# breakout_v0_4.net
KiCad netlist of a schematic drawn in EAGLE
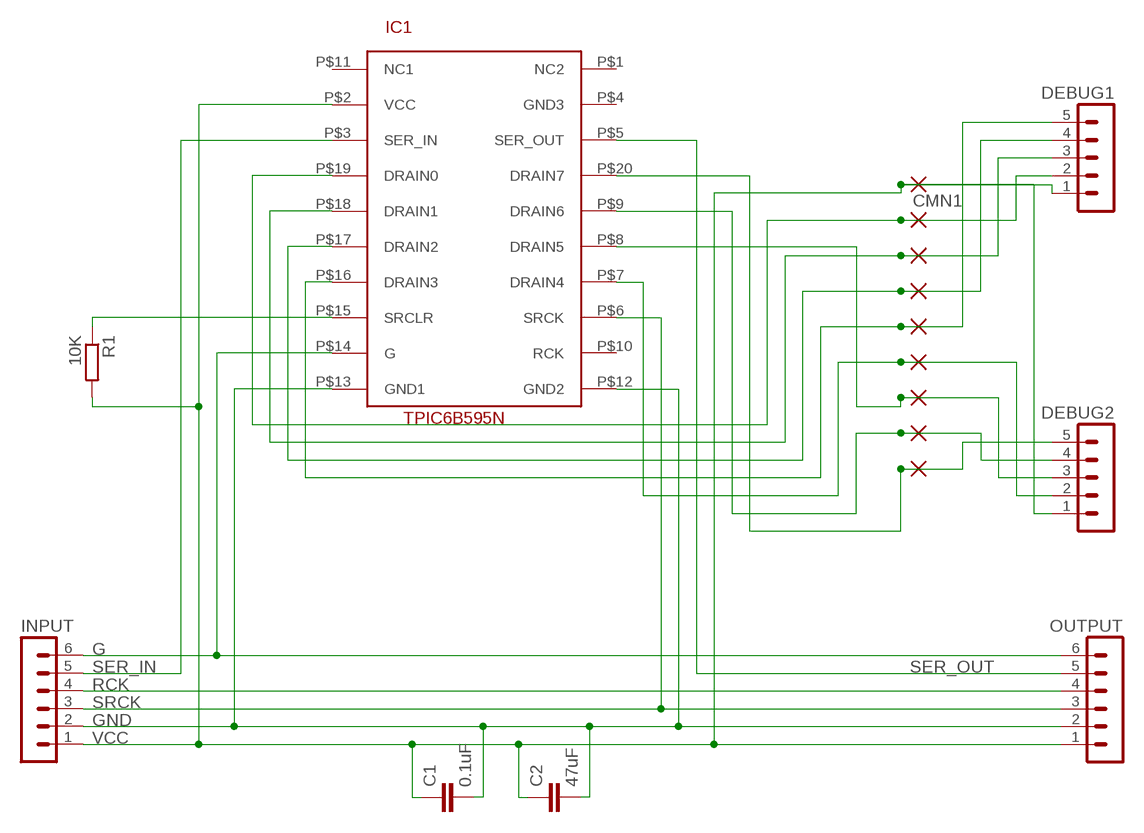
[diagram p0: schematic, sheet 1]

(export (version "E")
  (design (tool "Eeschema 10.0.6"))
  (components
    (comp (ref "C1")
      (value "0.1uF")
      (footprint "eagle-import:RCL_C025-025X050")
      (libsource (lib "eagle-import") (part "RCL_C-EU025-025X050"))
    )
    (comp (ref "C2")
      (value "47uF")
      (footprint "eagle-import:RCL_C025-025X050")
      (libsource (lib "eagle-import") (part "RCL_C-EU025-025X050"))
    )
    (comp (ref "CMN1")
      (value "1,6/0,8")
      (footprint "eagle-import:1,6_0,8")
      (libsource (lib "eagle-import") (part "1,6/0,8"))
    )
    (comp (ref "DEBUG1")
      (value "MA05-1")
      (footprint "eagle-import:MA05-1")
      (libsource (lib "eagle-import") (part "MA05-1"))
    )
    (comp (ref "DEBUG2")
      (value "MA05-1")
      (footprint "eagle-import:MA05-1")
      (libsource (lib "eagle-import") (part "MA05-1"))
    )
    (comp (ref "DEC1")
      (value "1,6/0,8")
      (footprint "eagle-import:1,6_0,8")
      (libsource (lib "eagle-import") (part "1,6/0,8"))
    )
    (comp (ref "INPUT")
      (value "CON-LSTB_MA06-1")
      (footprint "eagle-import:CON-LSTB_MA06-1")
      (libsource (lib "eagle-import") (part "CON-LSTB_MA06-1"))
    )
    (comp (ref "OUTPUT")
      (value "CON-LSTB_MA06-1")
      (footprint "eagle-import:CON-LSTB_MA06-1")
      (libsource (lib "eagle-import") (part "CON-LSTB_MA06-1"))
    )
    (comp (ref "R1")
      (value "10K")
      (footprint "eagle-import:RCL_0207_7")
      (libsource (lib "eagle-import") (part "RCL_R-EU_0207/7"))
    )
    (comp (ref "SEGA1")
      (value "1,6/0,8")
      (footprint "eagle-import:1,6_0,8")
      (libsource (lib "eagle-import") (part "1,6/0,8"))
    )
    (comp (ref "SEGB1")
      (value "1,6/0,8")
      (footprint "eagle-import:1,6_0,8")
      (libsource (lib "eagle-import") (part "1,6/0,8"))
    )
    (comp (ref "SEGC1")
      (value "1,6/0,8")
      (footprint "eagle-import:1,6_0,8")
      (libsource (lib "eagle-import") (part "1,6/0,8"))
    )
    (comp (ref "SEGD1")
      (value "1,6/0,8")
      (footprint "eagle-import:1,6_0,8")
      (libsource (lib "eagle-import") (part "1,6/0,8"))
    )
    (comp (ref "SEGE1")
      (value "1,6/0,8")
      (footprint "eagle-import:1,6_0,8")
      (libsource (lib "eagle-import") (part "1,6/0,8"))
    )
    (comp (ref "SEGF1")
      (value "1,6/0,8")
      (footprint "eagle-import:1,6_0,8")
      (libsource (lib "eagle-import") (part "1,6/0,8"))
    )
    (comp (ref "SEGG1")
      (value "1,6/0,8")
      (footprint "eagle-import:1,6_0,8")
      (libsource (lib "eagle-import") (part "1,6/0,8"))
    )
    (comp (ref "U$1")
      (value "TPIC6B595N_TPIC6B595NPDIP-20")
      (footprint "eagle-import:TPIC6B595N_PDIP-20")
      (libsource (lib "eagle-import") (part "TPIC6B595N_TPIC6B595NPDIP-20"))
    )
  )
  (nets
    (net (code "1") (name "/G") (class "Default")
      (node (ref "INPUT") (pin "6") (pinfunction "6_6") (pintype "passive"))
      (node (ref "OUTPUT") (pin "6") (pinfunction "6_6") (pintype "passive"))
      (node (ref "U$1") (pin "P$14") (pinfunction "G_P$14") (pintype "bidirectional"))
    )
    (net (code "2") (name "/GND") (class "Default")
      (node (ref "C1") (pin "2") (pinfunction "2_2") (pintype "passive"))
      (node (ref "C2") (pin "2") (pinfunction "2_2") (pintype "passive"))
      (node (ref "INPUT") (pin "2") (pinfunction "2_2") (pintype "passive"))
      (node (ref "OUTPUT") (pin "2") (pinfunction "2_2") (pintype "passive"))
      (node (ref "U$1") (pin "P$12") (pinfunction "GND2_P$12") (pintype "bidirectional"))
      (node (ref "U$1") (pin "P$13") (pinfunction "GND1_P$13") (pintype "bidirectional"))
    )
    (net (code "3") (name "/RCK") (class "Default")
      (node (ref "INPUT") (pin "4") (pinfunction "4_4") (pintype "passive"))
      (node (ref "OUTPUT") (pin "4") (pinfunction "4_4") (pintype "passive"))
    )
    (net (code "4") (name "/SER_IN") (class "Default")
      (node (ref "INPUT") (pin "5") (pinfunction "5_5") (pintype "passive"))
      (node (ref "U$1") (pin "P$3") (pinfunction "SER_IN_P$3") (pintype "bidirectional"))
    )
    (net (code "5") (name "/SER_OUT") (class "Default")
      (node (ref "OUTPUT") (pin "5") (pinfunction "5_5") (pintype "passive"))
      (node (ref "U$1") (pin "P$5") (pinfunction "SER_OUT_P$5") (pintype "bidirectional"))
    )
    (net (code "6") (name "/SRCK") (class "Default")
      (node (ref "INPUT") (pin "3") (pinfunction "3_3") (pintype "passive"))
      (node (ref "OUTPUT") (pin "3") (pinfunction "3_3") (pintype "passive"))
      (node (ref "U$1") (pin "P$6") (pinfunction "SRCK_P$6") (pintype "bidirectional"))
    )
    (net (code "7") (name "/VCC") (class "Default")
      (node (ref "C1") (pin "1") (pinfunction "1_1") (pintype "passive"))
      (node (ref "C2") (pin "1") (pinfunction "1_1") (pintype "passive"))
      (node (ref "CMN1") (pin "1") (pinfunction "P_1") (pintype "passive"))
      (node (ref "DEBUG1") (pin "1") (pinfunction "1_1") (pintype "passive"))
      (node (ref "DEBUG2") (pin "1") (pinfunction "1_1") (pintype "passive"))
      (node (ref "INPUT") (pin "1") (pinfunction "1_1") (pintype "passive"))
      (node (ref "OUTPUT") (pin "1") (pinfunction "1_1") (pintype "passive"))
      (node (ref "R1") (pin "2") (pinfunction "2_2") (pintype "passive"))
      (node (ref "U$1") (pin "P$2") (pinfunction "VCC_P$2") (pintype "bidirectional"))
    )
    (net (code "8") (name "Net-(DEC1-P)") (class "Default")
      (node (ref "DEBUG2") (pin "5") (pinfunction "5_5") (pintype "passive"))
      (node (ref "DEC1") (pin "1") (pinfunction "P_1") (pintype "passive"))
      (node (ref "U$1") (pin "P$20") (pinfunction "DRAIN7_P$20") (pintype "bidirectional"))
    )
    (net (code "9") (name "Net-(SEGA1-P)") (class "Default")
      (node (ref "DEBUG1") (pin "2") (pinfunction "2_2") (pintype "passive"))
      (node (ref "SEGA1") (pin "1") (pinfunction "P_1") (pintype "passive"))
      (node (ref "U$1") (pin "P$19") (pinfunction "DRAIN0_P$19") (pintype "bidirectional"))
    )
    (net (code "10") (name "Net-(SEGB1-P)") (class "Default")
      (node (ref "DEBUG1") (pin "3") (pinfunction "3_3") (pintype "passive"))
      (node (ref "SEGB1") (pin "1") (pinfunction "P_1") (pintype "passive"))
      (node (ref "U$1") (pin "P$18") (pinfunction "DRAIN1_P$18") (pintype "bidirectional"))
    )
    (net (code "11") (name "Net-(SEGC1-P)") (class "Default")
      (node (ref "DEBUG1") (pin "4") (pinfunction "4_4") (pintype "passive"))
      (node (ref "SEGC1") (pin "1") (pinfunction "P_1") (pintype "passive"))
      (node (ref "U$1") (pin "P$17") (pinfunction "DRAIN2_P$17") (pintype "bidirectional"))
    )
    (net (code "12") (name "Net-(SEGD1-P)") (class "Default")
      (node (ref "DEBUG1") (pin "5") (pinfunction "5_5") (pintype "passive"))
      (node (ref "SEGD1") (pin "1") (pinfunction "P_1") (pintype "passive"))
      (node (ref "U$1") (pin "P$16") (pinfunction "DRAIN3_P$16") (pintype "bidirectional"))
    )
    (net (code "13") (name "Net-(SEGE1-P)") (class "Default")
      (node (ref "DEBUG2") (pin "2") (pinfunction "2_2") (pintype "passive"))
      (node (ref "SEGE1") (pin "1") (pinfunction "P_1") (pintype "passive"))
      (node (ref "U$1") (pin "P$7") (pinfunction "DRAIN4_P$7") (pintype "bidirectional"))
    )
    (net (code "14") (name "Net-(SEGF1-P)") (class "Default")
      (node (ref "DEBUG2") (pin "3") (pinfunction "3_3") (pintype "passive"))
      (node (ref "SEGF1") (pin "1") (pinfunction "P_1") (pintype "passive"))
      (node (ref "U$1") (pin "P$8") (pinfunction "DRAIN5_P$8") (pintype "bidirectional"))
    )
    (net (code "15") (name "Net-(SEGG1-P)") (class "Default")
      (node (ref "DEBUG2") (pin "4") (pinfunction "4_4") (pintype "passive"))
      (node (ref "SEGG1") (pin "1") (pinfunction "P_1") (pintype "passive"))
      (node (ref "U$1") (pin "P$9") (pinfunction "DRAIN6_P$9") (pintype "bidirectional"))
    )
    (net (code "16") (name "Net-(U$1-SRCLR)") (class "Default")
      (node (ref "R1") (pin "1") (pinfunction "1_1") (pintype "passive"))
      (node (ref "U$1") (pin "P$15") (pinfunction "SRCLR_P$15") (pintype "bidirectional"))
    )
    (net (code "17") (name "unconnected-(U$1-GND3-PadP$4)") (class "Default")
      (node (ref "U$1") (pin "P$4") (pinfunction "GND3_P$4") (pintype "bidirectional"))
    )
    (net (code "18") (name "unconnected-(U$1-NC1-PadP$11)") (class "Default")
      (node (ref "U$1") (pin "P$11") (pinfunction "NC1_P$11") (pintype "bidirectional"))
    )
    (net (code "19") (name "unconnected-(U$1-NC2-PadP$1)") (class "Default")
      (node (ref "U$1") (pin "P$1") (pinfunction "NC2_P$1") (pintype "bidirectional"))
    )
    (net (code "20") (name "unconnected-(U$1-RCK-PadP$10)") (class "Default")
      (node (ref "U$1") (pin "P$10") (pinfunction "RCK_P$10") (pintype "bidirectional"))
    )
  )
)
